# MicroControllers.net
KiCad netlist of a schematic drawn in Altium Designer
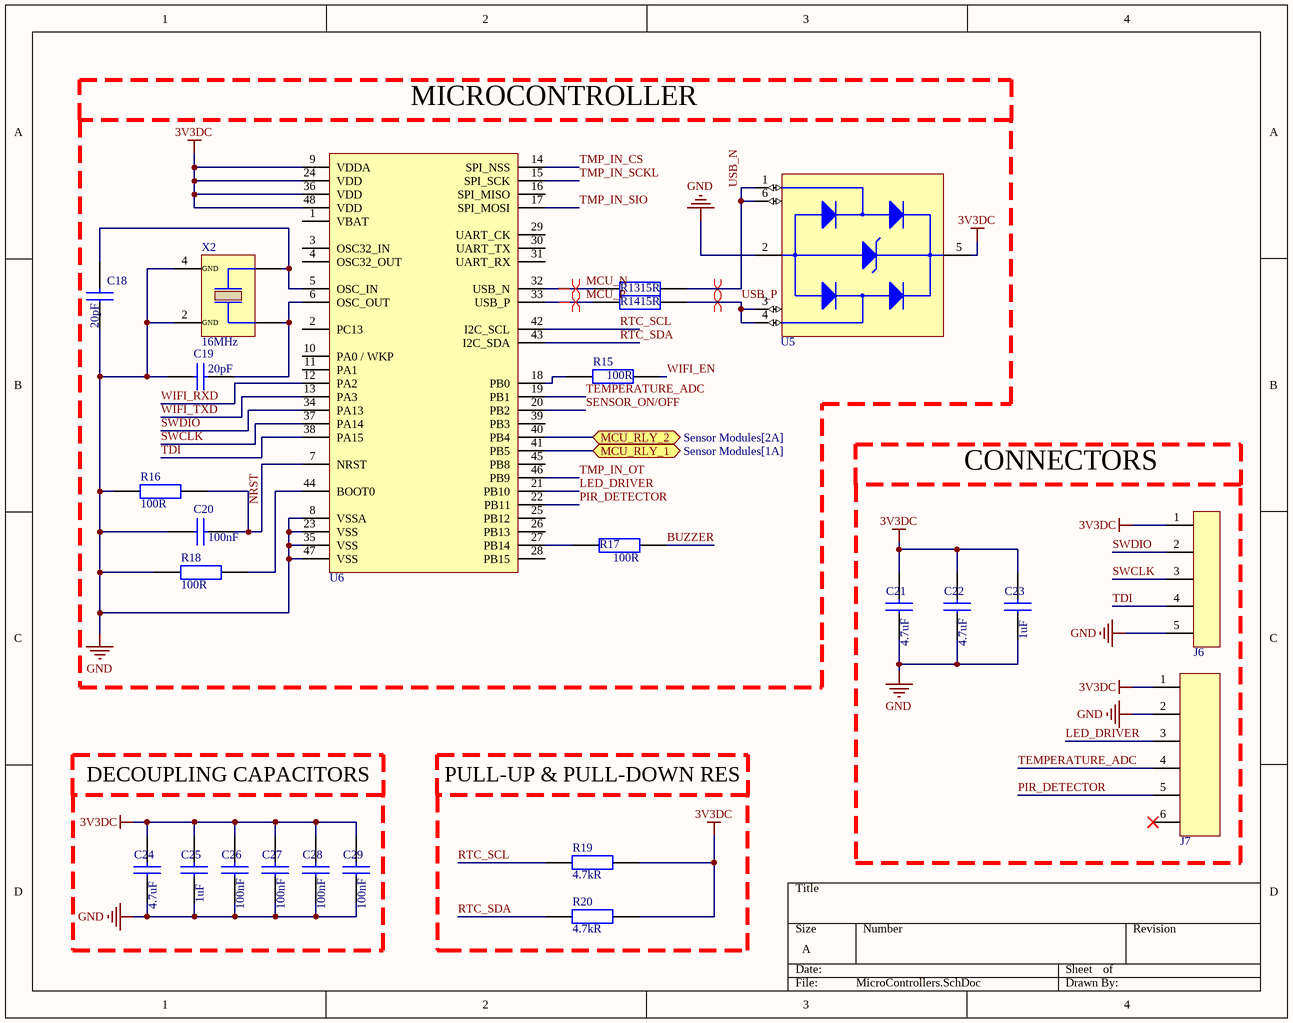
[diagram p0: MicroControllers.SchDoc]

(export (version "E")
  (design (tool "Eeschema 10.0.6"))
  (components
    (comp (ref "C18")
      (value "CL10C200JB8NNNC")
      (footprint "CAP_0603")
      (description "CAP CER 20pF %5 0603 SMD")
      (fields
        (field (name "MANUFACTURER") "Samsung")
        (field (name "TOLERANCE") "5%")
        (field (name "CAPACITANCE") "20pF")
        (field (name "DESIGNED BY") "BERK")
      )
      (libsource (lib "UDEMY_Library") (part "CAP CER 20pF 0603"))
    )
    (comp (ref "C19")
      (value "CL10C200JB8NNNC")
      (footprint "CAP_0603")
      (description "CAP CER 20pF %5 0603 SMD")
      (fields
        (field (name "MANUFACTURER") "Samsung")
        (field (name "TOLERANCE") "5%")
        (field (name "CAPACITANCE") "20pF")
        (field (name "DESIGNED BY") "BERK")
      )
      (libsource (lib "UDEMY_Library") (part "CAP CER 20pF 0603"))
    )
    (comp (ref "C20")
      (value "CL21B104KBCNNNC")
      (footprint "CAP_0805")
      (description "CAP CER 100nF %10 0805")
      (fields
        (field (name "MANUFACTURER") "Samsung")
        (field (name "TOLERANCE") "10%")
        (field (name "CAPACITANCE") "100nF")
        (field (name "DESIGNED BY") "BERK")
      )
      (libsource (lib "UDEMY_Library") (part "CAP CER 100nF 0805"))
    )
    (comp (ref "C21")
      (value "CL21A475KAQNNNE")
      (footprint "CAP_0805")
      (description "CAP CER 4.7uF %10 0805")
      (fields
        (field (name "MANUFACTURER") "Samsung")
        (field (name "TOLERANCE") "10%")
        (field (name "CAPACITANCE") "4.7uF")
        (field (name "DESIGNED BY") "BERK")
      )
      (libsource (lib "UDEMY_Library") (part "CAP CER 4.7uF 0805"))
    )
    (comp (ref "C22")
      (value "CL21A475KAQNNNE")
      (footprint "CAP_0805")
      (description "CAP CER 4.7uF %10 0805")
      (fields
        (field (name "MANUFACTURER") "Samsung")
        (field (name "TOLERANCE") "10%")
        (field (name "CAPACITANCE") "4.7uF")
        (field (name "DESIGNED BY") "BERK")
      )
      (libsource (lib "UDEMY_Library") (part "CAP CER 4.7uF 0805"))
    )
    (comp (ref "C23")
      (value "CL21B105KBFNNNE")
      (footprint "CAP_0805")
      (description "CAP CER 1uF %10 0805")
      (fields
        (field (name "MANUFACTURER") "Samsung")
        (field (name "TOLERANCE") "10%")
        (field (name "CAPACITANCE") "1uF")
        (field (name "DESIGNED BY") "BERK")
      )
      (libsource (lib "UDEMY_Library") (part "CAP CER 1uF 0805"))
    )
    (comp (ref "C24")
      (value "CL21A475KAQNNNE")
      (footprint "CAP_0805")
      (description "CAP CER 4.7uF %10 0805")
      (fields
        (field (name "MANUFACTURER") "Samsung")
        (field (name "TOLERANCE") "10%")
        (field (name "CAPACITANCE") "4.7uF")
        (field (name "DESIGNED BY") "BERK")
      )
      (libsource (lib "UDEMY_Library") (part "CAP CER 4.7uF 0805"))
    )
    (comp (ref "C25")
      (value "CL21B105KBFNNNE")
      (footprint "CAP_0805")
      (description "CAP CER 1uF %10 0805")
      (fields
        (field (name "MANUFACTURER") "Samsung")
        (field (name "TOLERANCE") "10%")
        (field (name "CAPACITANCE") "1uF")
        (field (name "DESIGNED BY") "BERK")
      )
      (libsource (lib "UDEMY_Library") (part "CAP CER 1uF 0805"))
    )
    (comp (ref "C26")
      (value "C0603C104K5RACTU")
      (footprint "CAP_0603")
      (description "CAP CER 100nF %10 0603 SMD")
      (fields
        (field (name "MANUFACTURER") "KEMET")
        (field (name "TOLERANCE") "10%")
        (field (name "CAPACITANCE") "100nF")
        (field (name "DESIGNED BY") "BERK")
      )
      (libsource (lib "UDEMY_Library") (part "CAP CER 100nF 0603"))
    )
    (comp (ref "C27")
      (value "C0603C104K5RACTU")
      (footprint "CAP_0603")
      (description "CAP CER 100nF %10 0603 SMD")
      (fields
        (field (name "MANUFACTURER") "KEMET")
        (field (name "TOLERANCE") "10%")
        (field (name "CAPACITANCE") "100nF")
        (field (name "DESIGNED BY") "BERK")
      )
      (libsource (lib "UDEMY_Library") (part "CAP CER 100nF 0603"))
    )
    (comp (ref "C28")
      (value "C0603C104K5RACTU")
      (footprint "CAP_0603")
      (description "CAP CER 100nF %10 0603 SMD")
      (fields
        (field (name "MANUFACTURER") "KEMET")
        (field (name "TOLERANCE") "10%")
        (field (name "CAPACITANCE") "100nF")
        (field (name "DESIGNED BY") "BERK")
      )
      (libsource (lib "UDEMY_Library") (part "CAP CER 100nF 0603"))
    )
    (comp (ref "C29")
      (value "C0603C104K5RACTU")
      (footprint "CAP_0603")
      (description "CAP CER 100nF %10 0603 SMD")
      (fields
        (field (name "MANUFACTURER") "KEMET")
        (field (name "TOLERANCE") "10%")
        (field (name "CAPACITANCE") "100nF")
        (field (name "DESIGNED BY") "BERK")
      )
      (libsource (lib "UDEMY_Library") (part "CAP CER 100nF 0603"))
    )
    (comp (ref "J6")
      (value "SMH-105-02-L-S")
      (footprint "PINHEADER1X5_RA")
      (description ".100 C.L. HORIZONTAL SMT SOCKET")
      (fields (field (name "MANUFACTURER") "Samtec") (field (name "DESIGNED BY") "BERK"))
      (libsource (lib "UDEMY_Library") (part "SMH-105-02-L-S"))
    )
    (comp (ref "J7")
      (value "64800611622")
      (footprint "64800611622")
      (description "1.50mm 6PIN Connector")
      (fields (field (name "MANUFACTURER") "Wurth Electronics"))
      (libsource (lib "UDEMY_Library") (part "64800611622_conn_6pin"))
    )
    (comp (ref "R13")
      (value "RC0603JR-0715RL")
      (footprint "RES_0603")
      (description "RES 15 %5 OHM 0603 SMD")
      (fields
        (field (name "MANUFACTURER") "Yageo")
        (field (name "TOLERANCE") "5%")
        (field (name "RESISTANCE") "15R")
        (field (name "DESIGNED BY") "BERK")
      )
      (libsource (lib "UDEMY_Library") (part "RES 15 OHM 0603"))
    )
    (comp (ref "R14")
      (value "RC0603JR-0715RL")
      (footprint "RES_0603")
      (description "RES 15 %5 OHM 0603 SMD")
      (fields
        (field (name "MANUFACTURER") "Yageo")
        (field (name "TOLERANCE") "5%")
        (field (name "RESISTANCE") "15R")
        (field (name "DESIGNED BY") "BERK")
      )
      (libsource (lib "UDEMY_Library") (part "RES 15 OHM 0603"))
    )
    (comp (ref "R15")
      (value "RC0603JR-07100RL")
      (footprint "RES_0603")
      (description "RES 100 %5 OHM 0603 SMD")
      (fields
        (field (name "MANUFACTURER") "Yageo")
        (field (name "TOLERANCE") "5%")
        (field (name "RESISTANCE") "100R")
        (field (name "DESIGNED BY") "BERK")
      )
      (libsource (lib "UDEMY_Library") (part "RES 100 OHM 0603"))
    )
    (comp (ref "R16")
      (value "RC0603JR-07100RL")
      (footprint "RES_0603")
      (description "RES 100 %5 OHM 0603 SMD")
      (fields
        (field (name "MANUFACTURER") "Yageo")
        (field (name "TOLERANCE") "5%")
        (field (name "RESISTANCE") "100R")
        (field (name "DESIGNED BY") "BERK")
      )
      (libsource (lib "UDEMY_Library") (part "RES 100 OHM 0603"))
    )
    (comp (ref "R17")
      (value "RC0603JR-07100RL")
      (footprint "RES_0603")
      (description "RES 100 %5 OHM 0603 SMD")
      (fields
        (field (name "MANUFACTURER") "Yageo")
        (field (name "TOLERANCE") "5%")
        (field (name "RESISTANCE") "100R")
        (field (name "DESIGNED BY") "BERK")
      )
      (libsource (lib "UDEMY_Library") (part "RES 100 OHM 0603"))
    )
    (comp (ref "R18")
      (value "RC0603JR-07100RL")
      (footprint "RES_0603")
      (description "RES 100 %5 OHM 0603 SMD")
      (fields
        (field (name "MANUFACTURER") "Yageo")
        (field (name "TOLERANCE") "5%")
        (field (name "RESISTANCE") "100R")
        (field (name "DESIGNED BY") "BERK")
      )
      (libsource (lib "UDEMY_Library") (part "RES 100 OHM 0603"))
    )
    (comp (ref "R19")
      (value "RC0603JR-074K7L")
      (footprint "RES_0603")
      (description "RES 4K7 %5 OHM 0603 SMD")
      (fields
        (field (name "MANUFACTURER") "Yageo")
        (field (name "TOLERANCE") "5%")
        (field (name "RESISTANCE") "4.7kR")
        (field (name "DESIGNED BY") "BERK")
      )
      (libsource (lib "UDEMY_Library") (part "RES 4K7 OHM 0603"))
    )
    (comp (ref "R20")
      (value "RC0603JR-074K7L")
      (footprint "RES_0603")
      (description "RES 4K7 %5 OHM 0603 SMD")
      (fields
        (field (name "MANUFACTURER") "Yageo")
        (field (name "TOLERANCE") "5%")
        (field (name "RESISTANCE") "4.7kR")
        (field (name "DESIGNED BY") "BERK")
      )
      (libsource (lib "UDEMY_Library") (part "RES 4K7 OHM 0603"))
    )
    (comp (ref "U5")
      (value "USBLC6-2SC6")
      (footprint "SOT23-6L")
      (description "TVS DIODE 5.25V 17V SOT23-6")
      (fields (field (name "MANUFACTURER") "STMicroelectronics") (field (name "DESIGNED BY") "BERK"))
      (libsource (lib "UDEMY_Library") (part "USB PROTECTION"))
    )
    (comp (ref "U6")
      (value "STM32F103C6T6A")
      (footprint "LQFP-48")
      (description "MCU 32-bit STM32F ARM Cortex M3 RISC 32KB Flash 2.5V/3.3V 48-Pin LQFP Tray")
      (fields (field (name "MANUFACTURER") "STMicroelectronics") (field (name "DESIGNED BY") "BERK"))
      (libsource (lib "UDEMY_Library") (part "STM32F103C6T6A"))
    )
    (comp (ref "X2")
      (value "ECS-160-20-30B-TR")
      (footprint "ECS")
      (description "CRYSTAL 16.0000MHZ 20PF SMD")
      (fields
        (field (name "MANUFACTURER") "ECS International")
        (field (name "TOLERANCE") "50ppm")
        (field (name "FREQUENCY") "16MHz")
        (field (name "DESIGNED BY") "BERK")
      )
      (libsource (lib "UDEMY_Library") (part "CRYSTAL 16MHz"))
    )
  )
  (nets
    (net (code "1") (name "/BUZZER") (class "Default")
      (node (ref "R17") (pin "2") (pinfunction "2_2") (pintype "passive"))
    )
    (net (code "2") (name "/LED_DRIVER") (class "Default")
      (node (ref "J7") (pin "3") (pintype "power_in"))
      (node (ref "U6") (pin "21") (pinfunction "PB10_21") (pintype "passive"))
    )
    (net (code "3") (name "/MCU_N") (class "Default")
      (node (ref "R13") (pin "1") (pinfunction "1_1") (pintype "passive"))
      (node (ref "U6") (pin "32") (pinfunction "USB_N_32") (pintype "passive"))
    )
    (net (code "4") (name "/MCU_P") (class "Default")
      (node (ref "R14") (pin "1") (pinfunction "1_1") (pintype "passive"))
      (node (ref "U6") (pin "33") (pinfunction "USB_P_33") (pintype "passive"))
    )
    (net (code "5") (name "/MCU_RLY_1") (class "Default")
      (node (ref "U6") (pin "41") (pinfunction "PB5_41") (pintype "passive"))
    )
    (net (code "6") (name "/MCU_RLY_2") (class "Default")
      (node (ref "U6") (pin "40") (pinfunction "PB4_40") (pintype "passive"))
    )
    (net (code "7") (name "/NRST") (class "Default")
      (node (ref "C20") (pin "2") (pinfunction "2_2") (pintype "passive"))
      (node (ref "R16") (pin "2") (pinfunction "2_2") (pintype "passive"))
      (node (ref "U6") (pin "7") (pinfunction "NRST_7") (pintype "passive"))
    )
    (net (code "8") (name "/PIR_DETECTOR") (class "Default")
      (node (ref "J7") (pin "5") (pintype "power_in"))
      (node (ref "U6") (pin "22") (pinfunction "PB11_22") (pintype "passive"))
    )
    (net (code "9") (name "/RTC_SCL") (class "Default")
      (node (ref "R19") (pin "1") (pinfunction "1_1") (pintype "passive"))
      (node (ref "U6") (pin "42") (pinfunction "I2C_SCL_42") (pintype "passive"))
    )
    (net (code "10") (name "/RTC_SDA") (class "Default")
      (node (ref "R20") (pin "1") (pinfunction "1_1") (pintype "passive"))
      (node (ref "U6") (pin "43") (pinfunction "I2C_SDA_43") (pintype "passive"))
    )
    (net (code "11") (name "/SENSOR_ON{slash}OFF") (class "Default")
      (node (ref "U6") (pin "20") (pinfunction "PB2_20") (pintype "passive"))
    )
    (net (code "12") (name "/SWCLK") (class "Default")
      (node (ref "J6") (pin "3") (pinfunction "3_3") (pintype "power_in"))
      (node (ref "U6") (pin "37") (pinfunction "PA14_37") (pintype "passive"))
    )
    (net (code "13") (name "/SWDIO") (class "Default")
      (node (ref "J6") (pin "2") (pinfunction "2_2") (pintype "power_in"))
      (node (ref "U6") (pin "34") (pinfunction "PA13_34") (pintype "passive"))
    )
    (net (code "14") (name "/TDI") (class "Default")
      (node (ref "J6") (pin "4") (pinfunction "4_4") (pintype "power_in"))
      (node (ref "U6") (pin "38") (pinfunction "PA15_38") (pintype "passive"))
    )
    (net (code "15") (name "/TEMPERATURE_ADC") (class "Default")
      (node (ref "J7") (pin "4") (pintype "power_in"))
      (node (ref "U6") (pin "19") (pinfunction "PB1_19") (pintype "passive"))
    )
    (net (code "16") (name "/TMP_IN_CS") (class "Default")
      (node (ref "U6") (pin "14") (pinfunction "SPI_NSS_14") (pintype "passive"))
    )
    (net (code "17") (name "/TMP_IN_OT") (class "Default")
      (node (ref "U6") (pin "46") (pinfunction "PB9_46") (pintype "passive"))
    )
    (net (code "18") (name "/TMP_IN_SCKL") (class "Default")
      (node (ref "U6") (pin "15") (pinfunction "SPI_SCK_15") (pintype "passive"))
    )
    (net (code "19") (name "/TMP_IN_SIO") (class "Default")
      (node (ref "U6") (pin "17") (pinfunction "SPI_MOSI_17") (pintype "passive"))
    )
    (net (code "20") (name "/USB_N") (class "Default")
      (node (ref "R13") (pin "2") (pinfunction "2_2") (pintype "passive"))
      (node (ref "U5") (pin "1") (pinfunction "I/O1_1") (pintype "bidirectional"))
      (node (ref "U5") (pin "6") (pinfunction "I/O1_6") (pintype "bidirectional"))
    )
    (net (code "21") (name "/USB_P") (class "Default")
      (node (ref "R14") (pin "2") (pinfunction "2_2") (pintype "passive"))
      (node (ref "U5") (pin "3") (pinfunction "I/O2_3") (pintype "bidirectional"))
      (node (ref "U5") (pin "4") (pinfunction "I/O2_4") (pintype "bidirectional"))
    )
    (net (code "22") (name "/WIFI_EN") (class "Default")
      (node (ref "R15") (pin "2") (pinfunction "2_2") (pintype "passive"))
    )
    (net (code "23") (name "/WIFI_RXD") (class "Default")
      (node (ref "U6") (pin "12") (pinfunction "PA2_12") (pintype "passive"))
    )
    (net (code "24") (name "/WIFI_TXD") (class "Default")
      (node (ref "U6") (pin "13") (pinfunction "PA3_13") (pintype "passive"))
    )
    (net (code "25") (name "3V3DC") (class "Default")
      (node (ref "C21") (pin "2") (pinfunction "2_2") (pintype "passive"))
      (node (ref "C22") (pin "2") (pinfunction "2_2") (pintype "passive"))
      (node (ref "C23") (pin "2") (pinfunction "2_2") (pintype "passive"))
      (node (ref "C24") (pin "2") (pinfunction "2_2") (pintype "passive"))
      (node (ref "C25") (pin "2") (pinfunction "2_2") (pintype "passive"))
      (node (ref "C26") (pin "2") (pinfunction "2_2") (pintype "passive"))
      (node (ref "C27") (pin "2") (pinfunction "2_2") (pintype "passive"))
      (node (ref "C28") (pin "2") (pinfunction "2_2") (pintype "passive"))
      (node (ref "C29") (pin "2") (pinfunction "2_2") (pintype "passive"))
      (node (ref "J6") (pin "1") (pinfunction "1_1") (pintype "power_in"))
      (node (ref "J7") (pin "1") (pintype "power_in"))
      (node (ref "R19") (pin "2") (pinfunction "2_2") (pintype "passive"))
      (node (ref "R20") (pin "2") (pinfunction "2_2") (pintype "passive"))
      (node (ref "U5") (pin "5") (pinfunction "VBUS_5") (pintype "power_in"))
      (node (ref "U6") (pin "24") (pinfunction "VDD_24") (pintype "passive"))
      (node (ref "U6") (pin "36") (pinfunction "VDD_36") (pintype "passive"))
      (node (ref "U6") (pin "48") (pinfunction "VDD_48") (pintype "passive"))
      (node (ref "U6") (pin "9") (pinfunction "VDDA_9") (pintype "passive"))
    )
    (net (code "26") (name "GND") (class "Default")
      (node (ref "C18") (pin "1") (pinfunction "1_1") (pintype "passive"))
      (node (ref "C19") (pin "1") (pinfunction "1_1") (pintype "passive"))
      (node (ref "C20") (pin "1") (pinfunction "1_1") (pintype "passive"))
      (node (ref "C21") (pin "1") (pinfunction "1_1") (pintype "passive"))
      (node (ref "C22") (pin "1") (pinfunction "1_1") (pintype "passive"))
      (node (ref "C23") (pin "1") (pinfunction "1_1") (pintype "passive"))
      (node (ref "C24") (pin "1") (pinfunction "1_1") (pintype "passive"))
      (node (ref "C25") (pin "1") (pinfunction "1_1") (pintype "passive"))
      (node (ref "C26") (pin "1") (pinfunction "1_1") (pintype "passive"))
      (node (ref "C27") (pin "1") (pinfunction "1_1") (pintype "passive"))
      (node (ref "C28") (pin "1") (pinfunction "1_1") (pintype "passive"))
      (node (ref "C29") (pin "1") (pinfunction "1_1") (pintype "passive"))
      (node (ref "J6") (pin "5") (pinfunction "5_5") (pintype "power_in"))
      (node (ref "J7") (pin "2") (pintype "power_in"))
      (node (ref "R16") (pin "1") (pinfunction "1_1") (pintype "passive"))
      (node (ref "R18") (pin "1") (pinfunction "1_1") (pintype "passive"))
      (node (ref "U5") (pin "2") (pinfunction "GND_2") (pintype "power_in"))
      (node (ref "U6") (pin "23") (pinfunction "VSS_23") (pintype "passive"))
      (node (ref "U6") (pin "35") (pinfunction "VSS_35") (pintype "passive"))
      (node (ref "U6") (pin "47") (pinfunction "VSS_47") (pintype "passive"))
      (node (ref "U6") (pin "8") (pinfunction "VSSA_8") (pintype "passive"))
      (node (ref "X2") (pin "2") (pinfunction "GND_2") (pintype "passive"))
      (node (ref "X2") (pin "4") (pinfunction "GND_4") (pintype "passive"))
    )
    (net (code "27") (name "Net-(U6-BOOT0)") (class "Default")
      (node (ref "R18") (pin "2") (pinfunction "2_2") (pintype "passive"))
      (node (ref "U6") (pin "44") (pinfunction "BOOT0_44") (pintype "passive"))
    )
    (net (code "28") (name "Net-(U6-OSC_IN)") (class "Default")
      (node (ref "C18") (pin "2") (pinfunction "2_2") (pintype "passive"))
      (node (ref "U6") (pin "5") (pinfunction "OSC_IN_5") (pintype "passive"))
      (node (ref "X2") (pin "3") (pinfunction "3_3") (pintype "passive"))
    )
    (net (code "29") (name "Net-(U6-OSC_OUT)") (class "Default")
      (node (ref "C19") (pin "2") (pinfunction "2_2") (pintype "passive"))
      (node (ref "U6") (pin "6") (pinfunction "OSC_OUT_6") (pintype "passive"))
      (node (ref "X2") (pin "1") (pinfunction "1_1") (pintype "passive"))
    )
    (net (code "30") (name "Net-(U6-PB0)") (class "Default")
      (node (ref "R15") (pin "1") (pinfunction "1_1") (pintype "passive"))
      (node (ref "U6") (pin "18") (pinfunction "PB0_18") (pintype "passive"))
    )
    (net (code "31") (name "Net-(U6-PB14)") (class "Default")
      (node (ref "R17") (pin "1") (pinfunction "1_1") (pintype "passive"))
      (node (ref "U6") (pin "27") (pinfunction "PB14_27") (pintype "passive"))
    )
    (net (code "32") (name "unconnected-(J7-Pad6)") (class "Default")
      (node (ref "J7") (pin "6") (pintype "power_in+no_connect"))
    )
    (net (code "33") (name "unconnected-(U6-OSC32_IN-Pad3)") (class "Default")
      (node (ref "U6") (pin "3") (pinfunction "OSC32_IN_3") (pintype "passive"))
    )
    (net (code "34") (name "unconnected-(U6-OSC32_OUT-Pad4)") (class "Default")
      (node (ref "U6") (pin "4") (pinfunction "OSC32_OUT_4") (pintype "passive"))
    )
    (net (code "35") (name "unconnected-(U6-PA0_{slash}_WKP-Pad10)") (class "Default")
      (node (ref "U6") (pin "10") (pinfunction "PA0_/_WKP_10") (pintype "passive"))
    )
    (net (code "36") (name "unconnected-(U6-PA1-Pad11)") (class "Default")
      (node (ref "U6") (pin "11") (pinfunction "PA1_11") (pintype "passive"))
    )
    (net (code "37") (name "unconnected-(U6-PB3-Pad39)") (class "Default")
      (node (ref "U6") (pin "39") (pinfunction "PB3_39") (pintype "passive"))
    )
    (net (code "38") (name "unconnected-(U6-PB8-Pad45)") (class "Default")
      (node (ref "U6") (pin "45") (pinfunction "PB8_45") (pintype "passive"))
    )
    (net (code "39") (name "unconnected-(U6-PB12-Pad25)") (class "Default")
      (node (ref "U6") (pin "25") (pinfunction "PB12_25") (pintype "passive"))
    )
    (net (code "40") (name "unconnected-(U6-PB13-Pad26)") (class "Default")
      (node (ref "U6") (pin "26") (pinfunction "PB13_26") (pintype "passive"))
    )
    (net (code "41") (name "unconnected-(U6-PB15-Pad28)") (class "Default")
      (node (ref "U6") (pin "28") (pinfunction "PB15_28") (pintype "passive"))
    )
    (net (code "42") (name "unconnected-(U6-PC13-Pad2)") (class "Default")
      (node (ref "U6") (pin "2") (pinfunction "PC13_2") (pintype "passive"))
    )
    (net (code "43") (name "unconnected-(U6-SPI_MISO-Pad16)") (class "Default")
      (node (ref "U6") (pin "16") (pinfunction "SPI_MISO_16") (pintype "passive"))
    )
    (net (code "44") (name "unconnected-(U6-UART_CK-Pad29)") (class "Default")
      (node (ref "U6") (pin "29") (pinfunction "UART_CK_29") (pintype "passive"))
    )
    (net (code "45") (name "unconnected-(U6-UART_RX-Pad31)") (class "Default")
      (node (ref "U6") (pin "31") (pinfunction "UART_RX_31") (pintype "passive"))
    )
    (net (code "46") (name "unconnected-(U6-UART_TX-Pad30)") (class "Default")
      (node (ref "U6") (pin "30") (pinfunction "UART_TX_30") (pintype "passive"))
    )
    (net (code "47") (name "unconnected-(U6-VBAT-Pad1)") (class "Default")
      (node (ref "U6") (pin "1") (pinfunction "VBAT_1") (pintype "passive"))
    )
  )
)
